# Output_Stages.net
KiCad netlist of a schematic drawn in Altium Designer
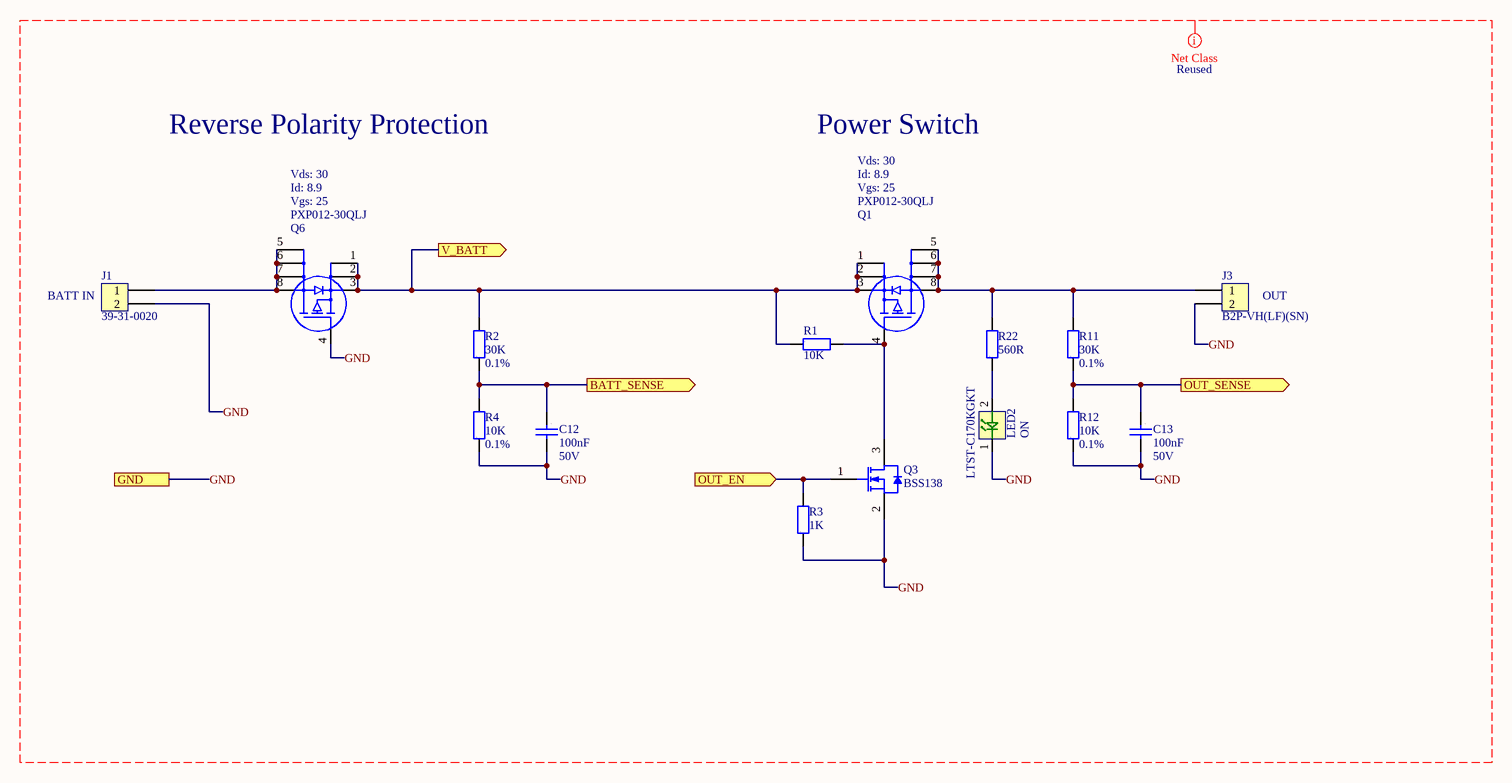
[diagram p0: Output Stages.SchDoc]

(export (version "E")
  (design (tool "Eeschema 10.0.6"))
  (components
    (comp (ref "C12")
      (value "100nF")
      (footprint "CAPC1608X08L")
      (description "Capacitor MLC 100nF 50V X7R 10% CAPC1608X08M")
      (fields
        (field (name "VOLTAGE") "50V")
        (field (name "MANUFACTURER") "Murata")
        (field (name "MANUPARTNO") "GRM188R71H104KA93D")
      )
      (libsource (lib "Library") (part "CAP"))
    )
    (comp (ref "C13")
      (value "100nF")
      (footprint "CAPC1608X08L")
      (description "Capacitor MLC 100nF 50V X7R 10% CAPC1608X08M")
      (fields
        (field (name "VOLTAGE") "50V")
        (field (name "MANUFACTURER") "Murata")
        (field (name "MANUPARTNO") "GRM188R71H104KA93D")
      )
      (libsource (lib "Library") (part "CAP"))
    )
    (comp (ref "J1")
      (value "BATT IN")
      (footprint "39-31-0020")
      (description "Connector 2 Way Mini-Fit 5566 Series")
      (fields (field (name "MANUPARTNO") "39-31-0020") (field (name "MANUFACTURER") "Molex"))
      (libsource (lib "Library") (part "CON2"))
    )
    (comp (ref "J3")
      (value "OUT")
      (footprint "B2P-VH")
      (description "Connector 2 Way Vertical JST B2P-VH(LF)(SN) 3.96mm Pitch")
      (fields (field (name "MANUPARTNO") "B2P-VH(LF)(SN)") (field (name "MANUFACTURER") "JST"))
      (libsource (lib "") (part "CON2_1"))
    )
    (comp (ref "LED2")
      (value "ON")
      (footprint "CAPCP2012X11N")
      (description "LED 2.0x1.25mm GREEN 0805 LTST-C170KGKT")
      (fields (field (name "MANUPARTNO") "LTST-C170KGKT") (field (name "MANUFACTURER") "Liteon"))
      (libsource (lib "Library") (part "LED_GREEN"))
    )
    (comp (ref "Q1")
      (value "Power Switch")
      (footprint "MLPAK33_SOT8002-1_NEX-M")
      (description "Power MOSFET, P Channel, 30 V, 15.2 A, 0.0111 ohm, MLPAK33, Surface Mount")
      (fields
        (field (name "MANUPARTNO") "PXP012-30QLJ")
        (field (name "VDS") "30")
        (field (name "ID") "8.9")
        (field (name "VGS") "25")
        (field (name "MANUFACTURER") "NEXPERIA")
      )
      (libsource (lib "Library") (part "FET_P_8"))
    )
    (comp (ref "Q3")
      (value "BSS138")
      (footprint "FAIR-SOT23-3_V")
      (fields (field (name "MANUFACTURER") "Fairchild") (field (name "POWER") "360mW"))
      (libsource (lib "Op Support Ltd") (part "NEMOS-GSD-3"))
    )
    (comp (ref "Q6")
      (value "Reverse Polarity Protection")
      (footprint "MLPAK33_SOT8002-1_NEX-M")
      (description "Power MOSFET, P Channel, 30 V, 15.2 A, 0.0111 ohm, MLPAK33, Surface Mount")
      (fields
        (field (name "MANUPARTNO") "PXP012-30QLJ")
        (field (name "VDS") "30")
        (field (name "ID") "8.9")
        (field (name "VGS") "25")
        (field (name "MANUFACTURER") "NEXPERIA")
      )
      (libsource (lib "") (part "FET_P_8_1"))
    )
    (comp (ref "R1")
      (value "10K")
      (footprint "RESC1608X06L")
      (description "SMD Chip Resistor, Thin Film, 10 kohm, 75 V, 0603 [1608 Metric], 100 mW, ± 0.1%, ERA3A Series")
      (fields (field (name "VOLTAGE") "75V") (field (name "MANUFACTURER") "Panasonic"))
      (libsource (lib "") (part "RESISTOR_1"))
    )
    (comp (ref "R2")
      (value "30K")
      (footprint "RESC1608X06L")
      (description "SMD Chip Resistor, Thin Film, 30 kohm, 75 V, 0603 [1608 Metric], 100 mW, ± 0.1%, ERA3A Series")
      (fields (field (name "TOLERANCE") "0.1%") (field (name "VOLTAGE") "75V") (field (name "POWER") "100mW"))
      (libsource (lib "Library") (part "RESISTOR"))
    )
    (comp (ref "R3")
      (value "1K")
      (footprint "RESC1608X06L")
      (description "SMD Chip Resistor, Thick Film, 1 kohm, 50 V, 0603 [1608 Metric], 100 mW, ± 1%, RC Series")
      (fields (field (name "VOLTAGE") "50V") (field (name "MANUFACTURER") "Yageo"))
      (libsource (lib "Library") (part "RESISTOR"))
    )
    (comp (ref "R4")
      (value "10K")
      (footprint "RESC1608X06L")
      (description "SMD Chip Resistor, Thin Film, 10 kohm, 75 V, 0603 [1608 Metric], 100 mW, ± 0.1%, ERA3A Series")
      (fields (field (name "TOLERANCE") "0.1%") (field (name "VOLTAGE") "75V") (field (name "POWER") "100mW"))
      (libsource (lib "Library") (part "RESISTOR"))
    )
    (comp (ref "R11")
      (value "30K")
      (footprint "RESC1608X06L")
      (description "SMD Chip Resistor, Thin Film, 30 kohm, 75 V, 0603 [1608 Metric], 100 mW, ± 0.1%, ERA3A Series")
      (fields (field (name "TOLERANCE") "0.1%") (field (name "VOLTAGE") "75V") (field (name "POWER") "100mW"))
      (libsource (lib "Library") (part "RESISTOR"))
    )
    (comp (ref "R12")
      (value "10K")
      (footprint "RESC1608X06L")
      (description "SMD Chip Resistor, Thin Film, 10 kohm, 75 V, 0603 [1608 Metric], 100 mW, ± 0.1%, ERA3A Series")
      (fields (field (name "TOLERANCE") "0.1%") (field (name "VOLTAGE") "75V") (field (name "POWER") "100mW"))
      (libsource (lib "Library") (part "RESISTOR"))
    )
    (comp (ref "R22")
      (value "560R")
      (footprint "RESC1608X06L")
      (description "Resistor 560R 1% 50V RESC1608X06M")
      (fields (field (name "VOLTAGE") "50V") (field (name "MANUFACTURER") "Multicomp"))
      (libsource (lib "Library") (part "RESISTOR"))
    )
  )
  (nets
    (net (code "1") (name "/BATT_SENSE") (class "Default")
      (node (ref "C12") (pin "1") (pinfunction "1_1") (pintype "passive"))
      (node (ref "R2") (pin "1") (pinfunction "1_1") (pintype "passive"))
      (node (ref "R4") (pin "2") (pinfunction "2_2") (pintype "passive"))
    )
    (net (code "2") (name "/GND") (class "Default")
      (node (ref "C12") (pin "2") (pinfunction "2_2") (pintype "passive"))
      (node (ref "C13") (pin "2") (pinfunction "2_2") (pintype "passive"))
      (node (ref "J1") (pin "2") (pinfunction "2_2") (pintype "passive"))
      (node (ref "J3") (pin "2") (pinfunction "2_2") (pintype "passive"))
      (node (ref "LED2") (pin "1") (pinfunction "1_1") (pintype "passive"))
      (node (ref "Q3") (pin "2") (pinfunction "S_2") (pintype "passive"))
      (node (ref "Q6") (pin "4") (pinfunction "Gate_4") (pintype "passive"))
      (node (ref "R12") (pin "1") (pinfunction "1_1") (pintype "passive"))
      (node (ref "R3") (pin "1") (pinfunction "1_1") (pintype "passive"))
      (node (ref "R4") (pin "1") (pinfunction "1_1") (pintype "passive"))
    )
    (net (code "3") (name "/OUT_EN") (class "Default")
      (node (ref "Q3") (pin "1") (pinfunction "G_1") (pintype "passive"))
      (node (ref "R3") (pin "2") (pinfunction "2_2") (pintype "passive"))
    )
    (net (code "4") (name "/OUT_SENSE") (class "Default")
      (node (ref "C13") (pin "1") (pinfunction "1_1") (pintype "passive"))
      (node (ref "R11") (pin "1") (pinfunction "1_1") (pintype "passive"))
      (node (ref "R12") (pin "2") (pinfunction "2_2") (pintype "passive"))
    )
    (net (code "5") (name "/V_BATT") (class "Default")
      (node (ref "Q1") (pin "1") (pinfunction "Source_1") (pintype "passive"))
      (node (ref "Q1") (pin "2") (pinfunction "Source_2") (pintype "passive"))
      (node (ref "Q1") (pin "3") (pinfunction "Source_3") (pintype "passive"))
      (node (ref "Q6") (pin "1") (pinfunction "Source_1") (pintype "passive"))
      (node (ref "Q6") (pin "2") (pinfunction "Source_2") (pintype "passive"))
      (node (ref "Q6") (pin "3") (pinfunction "Source_3") (pintype "passive"))
      (node (ref "R1") (pin "1") (pinfunction "1_1") (pintype "passive"))
      (node (ref "R2") (pin "2") (pinfunction "2_2") (pintype "passive"))
    )
    (net (code "6") (name "Net-(J1-Pad1)") (class "Default")
      (node (ref "J1") (pin "1") (pinfunction "1_1") (pintype "passive"))
      (node (ref "Q6") (pin "5") (pinfunction "Drain_5") (pintype "passive"))
      (node (ref "Q6") (pin "6") (pinfunction "Drain_6") (pintype "passive"))
      (node (ref "Q6") (pin "7") (pinfunction "Drain_7") (pintype "passive"))
      (node (ref "Q6") (pin "8") (pinfunction "Drain_8") (pintype "passive"))
    )
    (net (code "7") (name "Net-(J3-Pad1)") (class "Default")
      (node (ref "J3") (pin "1") (pinfunction "1_1") (pintype "passive"))
      (node (ref "Q1") (pin "5") (pinfunction "Drain_5") (pintype "passive"))
      (node (ref "Q1") (pin "6") (pinfunction "Drain_6") (pintype "passive"))
      (node (ref "Q1") (pin "7") (pinfunction "Drain_7") (pintype "passive"))
      (node (ref "Q1") (pin "8") (pinfunction "Drain_8") (pintype "passive"))
      (node (ref "R11") (pin "2") (pinfunction "2_2") (pintype "passive"))
      (node (ref "R22") (pin "2") (pinfunction "2_2") (pintype "passive"))
    )
    (net (code "8") (name "Net-(LED2-Pad2)") (class "Default")
      (node (ref "LED2") (pin "2") (pinfunction "2_2") (pintype "passive"))
      (node (ref "R22") (pin "1") (pinfunction "1_1") (pintype "passive"))
    )
    (net (code "9") (name "Net-(Q1-Gate)") (class "Default")
      (node (ref "Q1") (pin "4") (pinfunction "Gate_4") (pintype "passive"))
      (node (ref "Q3") (pin "3") (pinfunction "D_3") (pintype "passive"))
      (node (ref "R1") (pin "2") (pinfunction "2_2") (pintype "passive"))
    )
  )
)
